# DinoCalcPCB.net
KiCad netlist of a schematic drawn in EAGLE
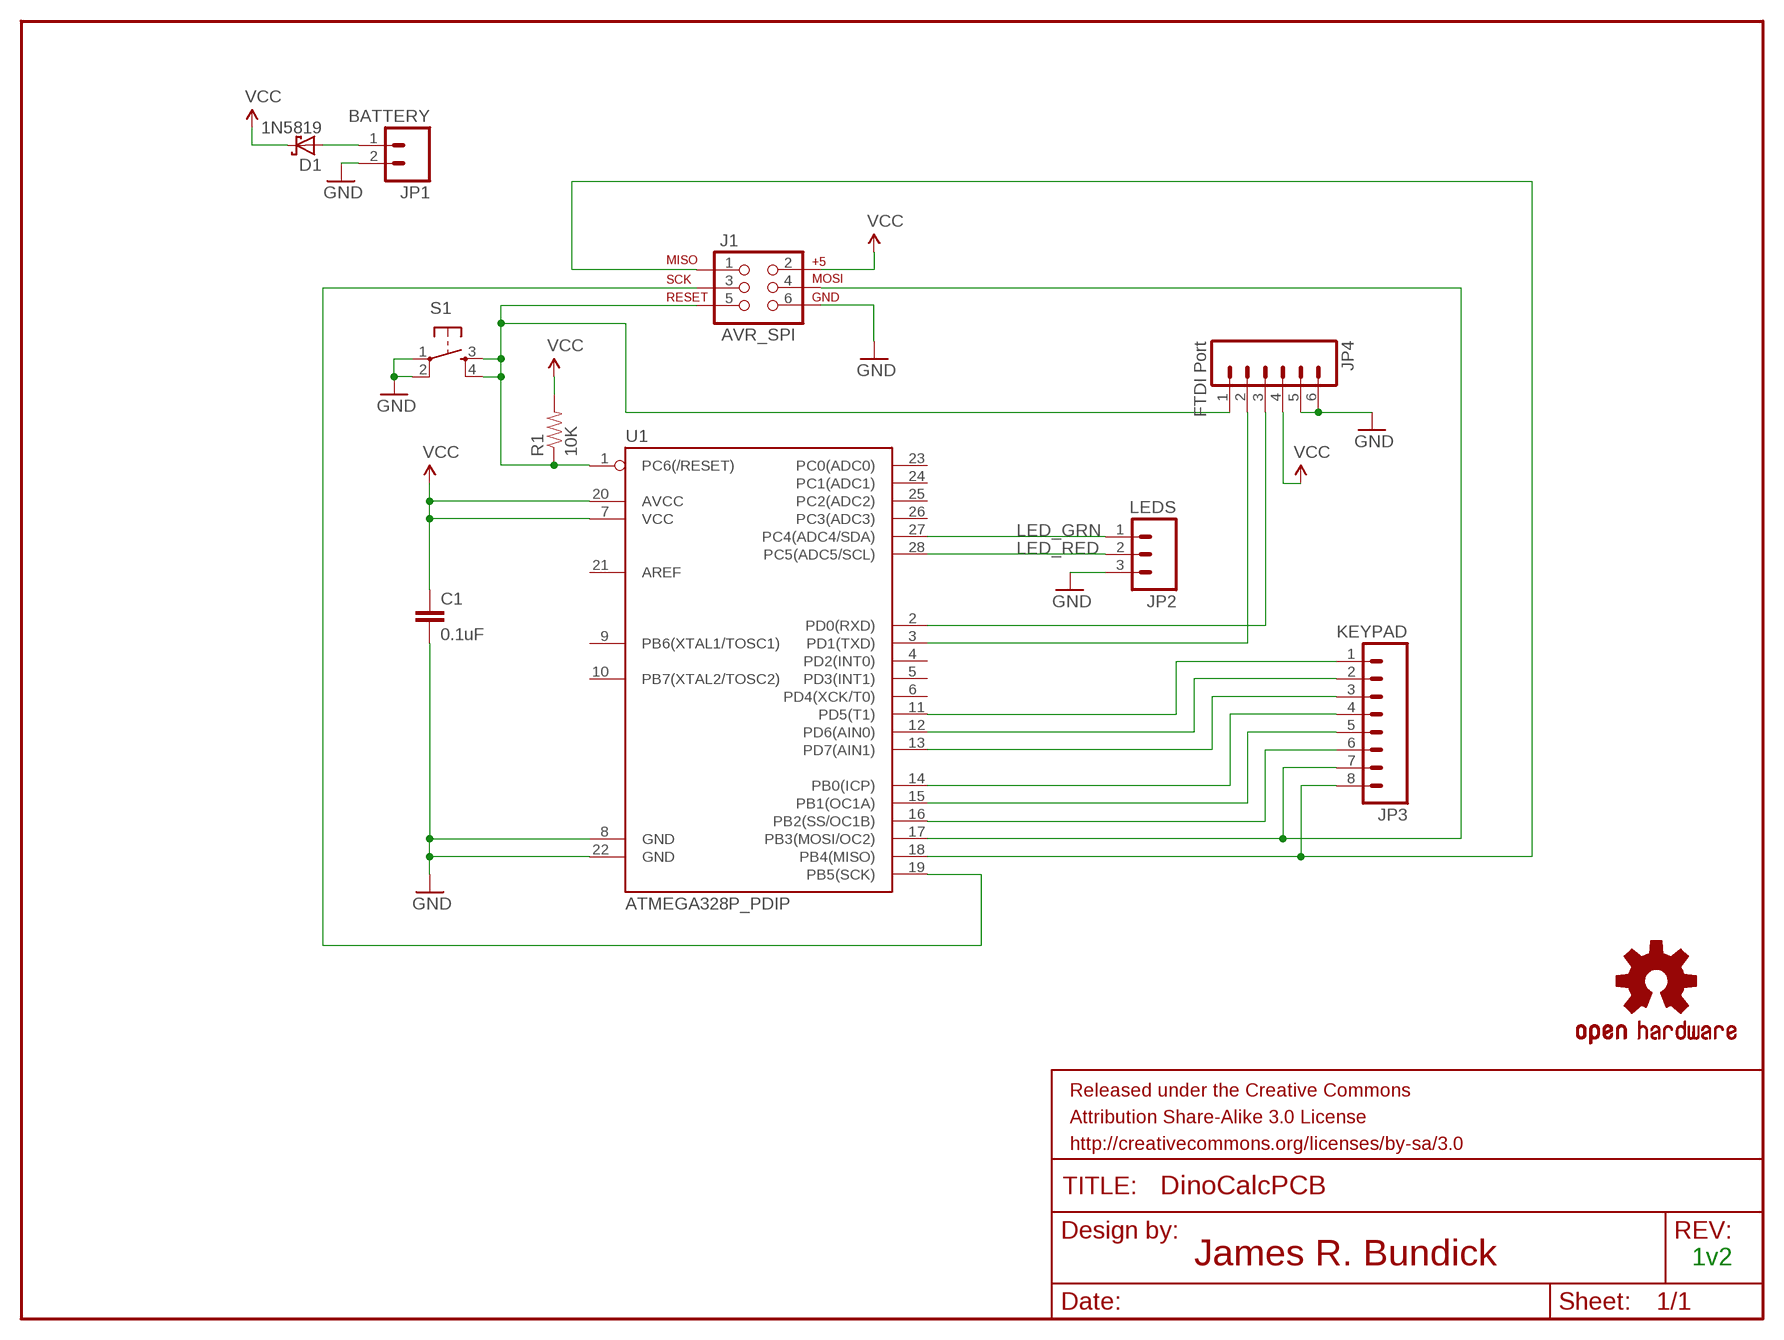
[diagram p0: schematic, sheet 1]

(export (version "E")
  (design (tool "Eeschema 10.0.6"))
  (components
    (comp (ref "C1")
      (value "0.1uF")
      (footprint "eagle-import:CAP-PTH-SMALL")
      (libsource (lib "eagle-import") (part "CAPPTH"))
    )
    (comp (ref "D1")
      (value "1N5819")
      (footprint "eagle-import:CB417-15")
      (libsource (lib "eagle-import") (part "SCHOTTKY-DIODECB417-15"))
    )
    (comp (ref "FRAME1")
      (value "FRAME-LETTER")
      (footprint "eagle-import:CREATIVE_COMMONS")
      (libsource (lib "eagle-import") (part "FRAME-LETTER"))
    )
    (comp (ref "J1")
      (value "AVR_SPI")
      (footprint "eagle-import:2X3_OFFSET")
      (libsource (lib "eagle-import") (part "AVR_SPI_PRG_6OFFSET_PADS"))
    )
    (comp (ref "JP1")
      (value "BATTERY")
      (footprint "eagle-import:1X02")
      (libsource (lib "eagle-import") (part "M02PTH"))
    )
    (comp (ref "JP2")
      (value "LEDS")
      (footprint "eagle-import:1X03")
      (libsource (lib "eagle-import") (part "M03PTH"))
    )
    (comp (ref "JP3")
      (value "KEYPAD")
      (footprint "eagle-import:1X08")
      (libsource (lib "eagle-import") (part "M081X08"))
    )
    (comp (ref "JP4")
      (value "FTDI Port")
      (footprint "eagle-import:1X06_LONGPADS")
      (libsource (lib "eagle-import") (part "M06LONGPADS"))
    )
    (comp (ref "LOGO1")
      (value "OSHW-LOGOL")
      (footprint "eagle-import:OSHW-LOGO-L")
      (libsource (lib "eagle-import") (part "OSHW-LOGOL"))
    )
    (comp (ref "R1")
      (value "10K")
      (footprint "eagle-import:AXIAL-0.4")
      (libsource (lib "eagle-import") (part "RESISTORPTH-1/4W"))
    )
    (comp (ref "S1")
      (value "TAC_SWITCHPTH")
      (footprint "eagle-import:TACTILE-PTH")
      (libsource (lib "eagle-import") (part "TAC_SWITCHPTH"))
    )
    (comp (ref "U1")
      (value "ATMEGA328P_PDIP")
      (footprint "eagle-import:DIL28-3")
      (libsource (lib "eagle-import") (part "ATMEGA328P_PDIP"))
    )
  )
  (nets
    (net (code "1") (name "/LED_GRN") (class "Default")
      (node (ref "JP2") (pin "1") (pinfunction "1_1") (pintype "passive"))
      (node (ref "U1") (pin "27") (pinfunction "PC4(ADC4/SDA)_27") (pintype "bidirectional"))
    )
    (net (code "2") (name "/LED_RED") (class "Default")
      (node (ref "JP2") (pin "2") (pinfunction "2_2") (pintype "passive"))
      (node (ref "U1") (pin "28") (pinfunction "PC5(ADC5/SCL)_28") (pintype "bidirectional"))
    )
    (net (code "3") (name "GND") (class "Default")
      (node (ref "C1") (pin "2") (pinfunction "2_2") (pintype "passive"))
      (node (ref "J1") (pin "6") (pinfunction "6_6") (pintype "passive"))
      (node (ref "JP1") (pin "2") (pinfunction "2_2") (pintype "passive"))
      (node (ref "JP2") (pin "3") (pinfunction "3_3") (pintype "passive"))
      (node (ref "JP4") (pin "5") (pinfunction "5_5") (pintype "passive"))
      (node (ref "JP4") (pin "6") (pinfunction "6_6") (pintype "passive"))
      (node (ref "S1") (pin "1") (pinfunction "1_1") (pintype "passive"))
      (node (ref "S1") (pin "2") (pinfunction "2_2") (pintype "passive"))
      (node (ref "U1") (pin "22") (pinfunction "GND_22") (pintype "bidirectional"))
      (node (ref "U1") (pin "8") (pinfunction "GND_8") (pintype "bidirectional"))
    )
    (net (code "4") (name "Net-(D1-PadA)") (class "Default")
      (node (ref "D1") (pin "A") (pinfunction "A_A") (pintype "passive"))
      (node (ref "JP1") (pin "1") (pinfunction "1_1") (pintype "passive"))
    )
    (net (code "5") (name "Net-(R1-1)") (class "Default")
      (node (ref "J1") (pin "5") (pinfunction "5_5") (pintype "passive"))
      (node (ref "JP4") (pin "1") (pinfunction "1_1") (pintype "passive"))
      (node (ref "R1") (pin "P$1") (pinfunction "1_P$1") (pintype "passive"))
      (node (ref "S1") (pin "3") (pinfunction "3_3") (pintype "passive"))
      (node (ref "S1") (pin "4") (pinfunction "4_4") (pintype "passive"))
      (node (ref "U1") (pin "1") (pinfunction "PC6(/RESET)_1") (pintype "bidirectional"))
    )
    (net (code "6") (name "Net-(U1-PB0(ICP))") (class "Default")
      (node (ref "JP3") (pin "4") (pinfunction "4_4") (pintype "passive"))
      (node (ref "U1") (pin "14") (pinfunction "PB0(ICP)_14") (pintype "bidirectional"))
    )
    (net (code "7") (name "Net-(U1-PB1(OC1A))") (class "Default")
      (node (ref "JP3") (pin "5") (pinfunction "5_5") (pintype "passive"))
      (node (ref "U1") (pin "15") (pinfunction "PB1(OC1A)_15") (pintype "bidirectional"))
    )
    (net (code "8") (name "Net-(U1-PB2(SS{slash}OC1B))") (class "Default")
      (node (ref "JP3") (pin "6") (pinfunction "6_6") (pintype "passive"))
      (node (ref "U1") (pin "16") (pinfunction "PB2(SS/OC1B)_16") (pintype "bidirectional"))
    )
    (net (code "9") (name "Net-(U1-PB3(MOSI{slash}OC2))") (class "Default")
      (node (ref "J1") (pin "4") (pinfunction "4_4") (pintype "passive"))
      (node (ref "JP3") (pin "7") (pinfunction "7_7") (pintype "passive"))
      (node (ref "U1") (pin "17") (pinfunction "PB3(MOSI/OC2)_17") (pintype "bidirectional"))
    )
    (net (code "10") (name "Net-(U1-PB4(MISO))") (class "Default")
      (node (ref "J1") (pin "1") (pinfunction "1_1") (pintype "passive"))
      (node (ref "JP3") (pin "8") (pinfunction "8_8") (pintype "passive"))
      (node (ref "U1") (pin "18") (pinfunction "PB4(MISO)_18") (pintype "bidirectional"))
    )
    (net (code "11") (name "Net-(U1-PB5(SCK))") (class "Default")
      (node (ref "J1") (pin "3") (pinfunction "3_3") (pintype "passive"))
      (node (ref "U1") (pin "19") (pinfunction "PB5(SCK)_19") (pintype "bidirectional"))
    )
    (net (code "12") (name "Net-(U1-PD0(RXD))") (class "Default")
      (node (ref "JP4") (pin "3") (pinfunction "3_3") (pintype "passive"))
      (node (ref "U1") (pin "2") (pinfunction "PD0(RXD)_2") (pintype "bidirectional"))
    )
    (net (code "13") (name "Net-(U1-PD1(TXD))") (class "Default")
      (node (ref "JP4") (pin "2") (pinfunction "2_2") (pintype "passive"))
      (node (ref "U1") (pin "3") (pinfunction "PD1(TXD)_3") (pintype "bidirectional"))
    )
    (net (code "14") (name "Net-(U1-PD5(T1))") (class "Default")
      (node (ref "JP3") (pin "1") (pinfunction "1_1") (pintype "passive"))
      (node (ref "U1") (pin "11") (pinfunction "PD5(T1)_11") (pintype "bidirectional"))
    )
    (net (code "15") (name "Net-(U1-PD6(AIN0))") (class "Default")
      (node (ref "JP3") (pin "2") (pinfunction "2_2") (pintype "passive"))
      (node (ref "U1") (pin "12") (pinfunction "PD6(AIN0)_12") (pintype "bidirectional"))
    )
    (net (code "16") (name "Net-(U1-PD7(AIN1))") (class "Default")
      (node (ref "JP3") (pin "3") (pinfunction "3_3") (pintype "passive"))
      (node (ref "U1") (pin "13") (pinfunction "PD7(AIN1)_13") (pintype "bidirectional"))
    )
    (net (code "17") (name "VCC") (class "Default")
      (node (ref "C1") (pin "1") (pinfunction "1_1") (pintype "passive"))
      (node (ref "D1") (pin "C") (pinfunction "C_C") (pintype "passive"))
      (node (ref "J1") (pin "2") (pinfunction "2_2") (pintype "passive"))
      (node (ref "JP4") (pin "4") (pinfunction "4_4") (pintype "passive"))
      (node (ref "R1") (pin "P$2") (pinfunction "2_P$2") (pintype "passive"))
      (node (ref "U1") (pin "20") (pinfunction "AVCC_20") (pintype "bidirectional"))
      (node (ref "U1") (pin "7") (pinfunction "VCC_7") (pintype "bidirectional"))
    )
    (net (code "18") (name "unconnected-(U1-AREF-Pad21)") (class "Default")
      (node (ref "U1") (pin "21") (pinfunction "AREF_21") (pintype "bidirectional"))
    )
    (net (code "19") (name "unconnected-(U1-PB6(XTAL1{slash}TOSC1)-Pad9)") (class "Default")
      (node (ref "U1") (pin "9") (pinfunction "PB6(XTAL1/TOSC1)_9") (pintype "bidirectional"))
    )
    (net (code "20") (name "unconnected-(U1-PB7(XTAL2{slash}TOSC2)-Pad10)") (class "Default")
      (node (ref "U1") (pin "10") (pinfunction "PB7(XTAL2/TOSC2)_10") (pintype "bidirectional"))
    )
    (net (code "21") (name "unconnected-(U1-PC0(ADC0)-Pad23)") (class "Default")
      (node (ref "U1") (pin "23") (pinfunction "PC0(ADC0)_23") (pintype "bidirectional"))
    )
    (net (code "22") (name "unconnected-(U1-PC1(ADC1)-Pad24)") (class "Default")
      (node (ref "U1") (pin "24") (pinfunction "PC1(ADC1)_24") (pintype "bidirectional"))
    )
    (net (code "23") (name "unconnected-(U1-PC2(ADC2)-Pad25)") (class "Default")
      (node (ref "U1") (pin "25") (pinfunction "PC2(ADC2)_25") (pintype "bidirectional"))
    )
    (net (code "24") (name "unconnected-(U1-PC3(ADC3)-Pad26)") (class "Default")
      (node (ref "U1") (pin "26") (pinfunction "PC3(ADC3)_26") (pintype "bidirectional"))
    )
    (net (code "25") (name "unconnected-(U1-PD2(INT0)-Pad4)") (class "Default")
      (node (ref "U1") (pin "4") (pinfunction "PD2(INT0)_4") (pintype "bidirectional"))
    )
    (net (code "26") (name "unconnected-(U1-PD3(INT1)-Pad5)") (class "Default")
      (node (ref "U1") (pin "5") (pinfunction "PD3(INT1)_5") (pintype "bidirectional"))
    )
    (net (code "27") (name "unconnected-(U1-PD4(XCK{slash}T0)-Pad6)") (class "Default")
      (node (ref "U1") (pin "6") (pinfunction "PD4(XCK/T0)_6") (pintype "bidirectional"))
    )
  )
)
